# W-F-FC-HX3X.net
KiCad netlist of a schematic drawn in Altium Designer
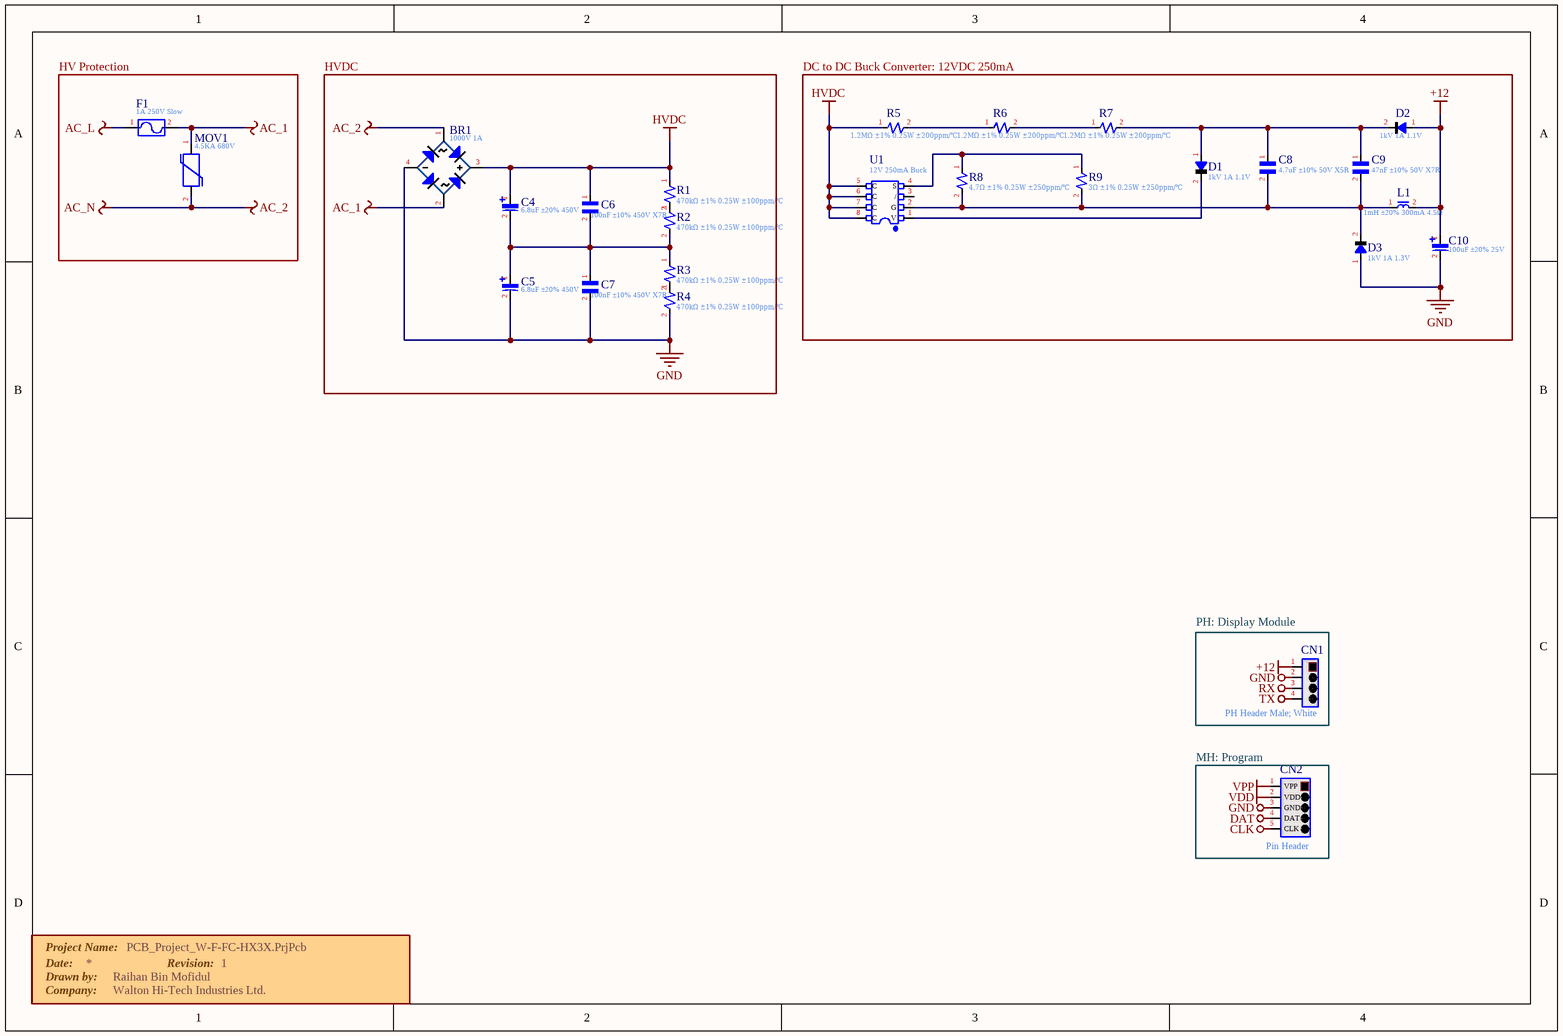
[diagram p0: W-F-FC-HX3X.SchDoc]

(export (version "E")
  (design (tool "Eeschema 10.0.6"))
  (components
    (comp (ref "BR1")
      (value "1000V 1A")
      (footprint "D_SMD_MBS")
      (description "MB10S-10; MBS Bridge Rectifiers RoHS")
      (libsource (lib "RBM_ALTIUM_SCH_LIBRARY") (part "Diode{gt}{gt} Bridge Rectifier"))
    )
    (comp (ref "C4")
      (value "6.8uF ±20% 450V")
      (footprint "C_SMD_Ø10*13mm")
      (description "VKME1302W6R8MV; 10x13mm Aluminum Electrolytic Capacitors - SMD RoHS")
      (libsource (lib "RBM_ALTIUM_SCH_LIBRARY") (part "Capacitor{gt}{gt} Polar"))
    )
    (comp (ref "C5")
      (value "6.8uF ±20% 450V")
      (footprint "C_SMD_Ø10*13mm")
      (description "VKME1302W6R8MV; 10x13mm Aluminum Electrolytic Capacitors - SMD RoHS")
      (libsource (lib "RBM_ALTIUM_SCH_LIBRARY") (part "Capacitor{gt}{gt} Polar"))
    )
    (comp (ref "C6")
      (value "100nF ±10% 450V X7R")
      (footprint "C_1206")
      (description "NM1206B104K451CEGN; 1206 Multilayer Ceramic Capacitors MLCC - SMD/SMT RoHS")
      (libsource (lib "RBM_ALTIUM_SCH_LIBRARY") (part "Capacitor{gt}{gt} Non-Polar"))
    )
    (comp (ref "C7")
      (value "100nF ±10% 450V X7R")
      (footprint "C_1206")
      (description "NM1206B104K451CEGN; 1206 Multilayer Ceramic Capacitors MLCC - SMD/SMT RoHS")
      (libsource (lib "RBM_ALTIUM_SCH_LIBRARY") (part "Capacitor{gt}{gt} Non-Polar"))
    )
    (comp (ref "C8")
      (value "4.7uF ±10% 50V X5R")
      (footprint "C_0805")
      (description "CL21A475KBQNNNE; 0805 Multilayer Ceramic Capacitors MLCC - SMD/SMT RoHS")
      (libsource (lib "RBM_ALTIUM_SCH_LIBRARY") (part "Capacitor{gt}{gt} Non-Polar"))
    )
    (comp (ref "C9")
      (value "47nF ±10% 50V X7R")
      (footprint "C_0805")
      (description "CL21B473KBANNNC; 0805 Multilayer Ceramic Capacitors MLCC - SMD/SMT RoHS")
      (libsource (lib "RBM_ALTIUM_SCH_LIBRARY") (part "Capacitor{gt}{gt} Non-Polar"))
    )
    (comp (ref "C10")
      (value "100uF ±20% 25V")
      (footprint "C_SMD_Ø6.3*5.4mm")
      (description "SMD,6.3x5.4mm Aluminum Electrolytic Capacitors - SMD RoHS")
      (libsource (lib "RBM_ALTIUM_SCH_LIBRARY") (part "Capacitor{gt}{gt} Polar"))
    )
    (comp (ref "CN1")
      (value "PH Header Male; White")
      (footprint "CN_4P_A2001WR-S-XP-LCP")
      (description "A2001WR-S-4P; Pin 0.079\"(2.00mm) 4 SMD,P=2mm Wire To Board / Wire To Wire Connector RoHS")
      (libsource (lib "RBM_ALTIUM_SCH_LIBRARY") (part "Connector{gt}{gt} 4Pins"))
    )
    (comp (ref "CN2")
      (value "Pin Header")
      (footprint "CN_PIC_MCU_Debugger_RightAngle")
      (libsource (lib "RBM_ALTIUM_SCH_LIBRARY") (part "Connector{gt}{gt} PIC Program"))
    )
    (comp (ref "D1")
      (value "1kV 1A 1.1V")
      (footprint "D_DO-214AC")
      (description "MDD  M7; SMA(DO-214AC) Diodes - General Purpose RoHS")
      (libsource (lib "RBM_ALTIUM_SCH_LIBRARY") (part "Diode{gt}{gt} General Purpose"))
    )
    (comp (ref "D2")
      (value "1kV 1A 1.1V")
      (footprint "D_DO-214AC")
      (description "MDD  M7; SMA(DO-214AC) Diodes - General Purpose RoHS")
      (libsource (lib "") (part "Diode{gt}{gt} General Purpose_1"))
    )
    (comp (ref "D3")
      (value "1kV 1A 1.3V")
      (footprint "D_DO-214AC")
      (description "LGE RS1M; 1A 500ns SMA Diodes - Rectifiers - Fast Recovery RoHS")
      (libsource (lib "") (part "Diode{gt}{gt} General Purpose_2"))
    )
    (comp (ref "F1")
      (value "1A 250V Slow")
      (footprint "F_SQUARE_8.5*8_P5.08")
      (libsource (lib "RBM_ALTIUM_SCH_LIBRARY") (part "Fuse"))
    )
    (comp (ref "L1")
      (value "1mH ±20% 300mA 4.5Ω")
      (footprint "L_SMD_6.0x6.0x4.5mm")
      (description "YNR6045-102M; SMD,6.0x6.0x4.5mm Power Inductors RoHS")
      (libsource (lib "RBM_ALTIUM_SCH_LIBRARY") (part "Inductor{gt}{gt} General Purpose"))
    )
    (comp (ref "MOV1")
      (value "4.5KA 680V")
      (footprint "MOV_14D561K")
      (description "VDR-14D681K; 560V 1120V 4.5KA 680V Through Hole,P=7.5MM Varistors RoHS")
      (libsource (lib "RBM_ALTIUM_SCH_LIBRARY") (part "Varistor"))
    )
    (comp (ref "R1")
      (value "470kΩ ±1% 0.25W ±100ppm/℃")
      (footprint "R_1206")
      (description "RK73H2BTTD4703F; 1206 Chip Resistor - Surface Mount RoHS")
      (libsource (lib "RBM_ALTIUM_SCH_LIBRARY") (part "Resistor{gt}{gt} General Purpose"))
    )
    (comp (ref "R2")
      (value "470kΩ ±1% 0.25W ±100ppm/℃")
      (footprint "R_1206")
      (description "RK73H2BTTD4703F; 1206 Chip Resistor - Surface Mount RoHS")
      (libsource (lib "RBM_ALTIUM_SCH_LIBRARY") (part "Resistor{gt}{gt} General Purpose"))
    )
    (comp (ref "R3")
      (value "470kΩ ±1% 0.25W ±100ppm/℃")
      (footprint "R_1206")
      (description "RK73H2BTTD4703F; 1206 Chip Resistor - Surface Mount RoHS")
      (libsource (lib "RBM_ALTIUM_SCH_LIBRARY") (part "Resistor{gt}{gt} General Purpose"))
    )
    (comp (ref "R4")
      (value "470kΩ ±1% 0.25W ±100ppm/℃")
      (footprint "R_1206")
      (description "RK73H2BTTD4703F; 1206 Chip Resistor - Surface Mount RoHS")
      (libsource (lib "RBM_ALTIUM_SCH_LIBRARY") (part "Resistor{gt}{gt} General Purpose"))
    )
    (comp (ref "R5")
      (value "1.2MΩ ±1% 0.25W ±200ppm/℃")
      (footprint "R_1206")
      (description "RK73H2BTTD1204F; 1206 Chip Resistor - Surface Mount RoHS")
      (libsource (lib "RBM_ALTIUM_SCH_LIBRARY") (part "Resistor{gt}{gt} General Purpose"))
    )
    (comp (ref "R6")
      (value "1.2MΩ ±1% 0.25W ±200ppm/℃")
      (footprint "R_1206")
      (description "RK73H2BTTD1204F; 1206 Chip Resistor - Surface Mount RoHS")
      (libsource (lib "RBM_ALTIUM_SCH_LIBRARY") (part "Resistor{gt}{gt} General Purpose"))
    )
    (comp (ref "R7")
      (value "1.2MΩ ±1% 0.25W ±200ppm/℃")
      (footprint "R_1206")
      (description "RK73H2BTTD1204F; 1206 Chip Resistor - Surface Mount RoHS")
      (libsource (lib "RBM_ALTIUM_SCH_LIBRARY") (part "Resistor{gt}{gt} General Purpose"))
    )
    (comp (ref "R8")
      (value "4.7Ω ±1% 0.25W ±250ppm/℃")
      (footprint "R_1206")
      (description "RS-06L4R70FT; 1206 Chip Resistor - Surface Mount RoHS")
      (libsource (lib "RBM_ALTIUM_SCH_LIBRARY") (part "Resistor{gt}{gt} General Purpose"))
    )
    (comp (ref "R9")
      (value "3Ω ±1% 0.25W ±250ppm/℃")
      (footprint "R_1206")
      (description "RS-06L3R00FT; 1206 Chip Resistor - Surface Mount RoHS")
      (libsource (lib "RBM_ALTIUM_SCH_LIBRARY") (part "Resistor{gt}{gt} General Purpose"))
    )
    (comp (ref "U1")
      (value "12V 250mA Buck")
      (footprint "U_SOP-8")
      (description "OB2225MCPA; SOP8 Switching Controllers RoHS")
      (libsource (lib "RBM_ALTIUM_SCH_LIBRARY") (part "IC{gt}{gt} OB-SMPS 8pins"))
    )
  )
  (nets
    (net (code "1") (name "+12") (class "Default")
      (node (ref "C10") (pin "1") (pinfunction "1_1") (pintype "passive"))
      (node (ref "CN1") (pin "1") (pinfunction "1_1") (pintype "passive"))
      (node (ref "D2") (pin "1") (pinfunction "A_1") (pintype "passive"))
      (node (ref "L1") (pin "2") (pinfunction "2_2") (pintype "passive"))
    )
    (net (code "2") (name "AC_1") (class "Default")
      (node (ref "BR1") (pin "2") (pinfunction "AC_2") (pintype "passive"))
      (node (ref "F1") (pin "2") (pinfunction "2_2") (pintype "passive"))
      (node (ref "MOV1") (pin "1") (pinfunction "1_1") (pintype "passive"))
    )
    (net (code "3") (name "AC_2") (class "Default")
      (node (ref "BR1") (pin "1") (pinfunction "AC_1") (pintype "passive"))
      (node (ref "MOV1") (pin "2") (pinfunction "2_2") (pintype "passive"))
    )
    (net (code "4") (name "AC_L") (class "Default")
      (node (ref "F1") (pin "1") (pinfunction "1_1") (pintype "passive"))
    )
    (net (code "5") (name "CLK") (class "Default")
      (node (ref "CN2") (pin "5") (pinfunction "CLK_5") (pintype "passive"))
    )
    (net (code "6") (name "DAT") (class "Default")
      (node (ref "CN2") (pin "4") (pinfunction "DAT_4") (pintype "passive"))
    )
    (net (code "7") (name "GND") (class "Default")
      (node (ref "BR1") (pin "4") (pinfunction "vss_4") (pintype "passive"))
      (node (ref "C10") (pin "2") (pinfunction "2_2") (pintype "passive"))
      (node (ref "C5") (pin "2") (pinfunction "2_2") (pintype "passive"))
      (node (ref "C7") (pin "2") (pinfunction "2_2") (pintype "passive"))
      (node (ref "CN1") (pin "2") (pinfunction "2_2") (pintype "passive"))
      (node (ref "CN2") (pin "3") (pinfunction "GND_3") (pintype "passive"))
      (node (ref "D3") (pin "1") (pinfunction "A_1") (pintype "passive"))
      (node (ref "R4") (pin "2") (pinfunction "2_2") (pintype "passive"))
    )
    (net (code "8") (name "HVDC") (class "Default")
      (node (ref "BR1") (pin "3") (pinfunction "VCC_3") (pintype "passive"))
      (node (ref "C4") (pin "1") (pinfunction "1_1") (pintype "passive"))
      (node (ref "C6") (pin "1") (pinfunction "1_1") (pintype "passive"))
      (node (ref "R1") (pin "1") (pinfunction "1_1") (pintype "passive"))
      (node (ref "R5") (pin "1") (pinfunction "1_1") (pintype "passive"))
      (node (ref "U1") (pin "5") (pinfunction "C_5") (pintype "passive"))
      (node (ref "U1") (pin "6") (pinfunction "C_6") (pintype "passive"))
      (node (ref "U1") (pin "7") (pinfunction "C_7") (pintype "passive"))
      (node (ref "U1") (pin "8") (pinfunction "C_8") (pintype "passive"))
    )
    (net (code "9") (name "Net-(C4-Pad2)") (class "Default")
      (node (ref "C4") (pin "2") (pinfunction "2_2") (pintype "passive"))
      (node (ref "C5") (pin "1") (pinfunction "1_1") (pintype "passive"))
      (node (ref "C6") (pin "2") (pinfunction "2_2") (pintype "passive"))
      (node (ref "C7") (pin "1") (pinfunction "1_1") (pintype "passive"))
      (node (ref "R2") (pin "2") (pinfunction "2_2") (pintype "passive"))
      (node (ref "R3") (pin "1") (pinfunction "1_1") (pintype "passive"))
    )
    (net (code "10") (name "Net-(D1-A)") (class "Default")
      (node (ref "C8") (pin "1") (pinfunction "1_1") (pintype "passive"))
      (node (ref "C9") (pin "1") (pinfunction "1_1") (pintype "passive"))
      (node (ref "D1") (pin "1") (pinfunction "A_1") (pintype "passive"))
      (node (ref "D2") (pin "2") (pinfunction "K_2") (pintype "passive"))
      (node (ref "R7") (pin "2") (pinfunction "2_2") (pintype "passive"))
    )
    (net (code "11") (name "Net-(D1-K)") (class "Default")
      (node (ref "D1") (pin "2") (pinfunction "K_2") (pintype "passive"))
      (node (ref "U1") (pin "1") (pinfunction "V_1") (pintype "passive"))
    )
    (net (code "12") (name "Net-(D3-K)") (class "Default")
      (node (ref "C8") (pin "2") (pinfunction "2_2") (pintype "passive"))
      (node (ref "C9") (pin "2") (pinfunction "2_2") (pintype "passive"))
      (node (ref "D3") (pin "2") (pinfunction "K_2") (pintype "passive"))
      (node (ref "L1") (pin "1") (pinfunction "1_1") (pintype "passive"))
      (node (ref "R8") (pin "2") (pinfunction "2_2") (pintype "passive"))
      (node (ref "R9") (pin "2") (pinfunction "2_2") (pintype "passive"))
      (node (ref "U1") (pin "2") (pinfunction "G_2") (pintype "passive"))
    )
    (net (code "13") (name "Net-(R1-Pad2)") (class "Default")
      (node (ref "R1") (pin "2") (pinfunction "2_2") (pintype "passive"))
      (node (ref "R2") (pin "1") (pinfunction "1_1") (pintype "passive"))
    )
    (net (code "14") (name "Net-(R3-Pad2)") (class "Default")
      (node (ref "R3") (pin "2") (pinfunction "2_2") (pintype "passive"))
      (node (ref "R4") (pin "1") (pinfunction "1_1") (pintype "passive"))
    )
    (net (code "15") (name "Net-(R5-Pad2)") (class "Default")
      (node (ref "R5") (pin "2") (pinfunction "2_2") (pintype "passive"))
      (node (ref "R6") (pin "1") (pinfunction "1_1") (pintype "passive"))
    )
    (net (code "16") (name "Net-(R6-Pad2)") (class "Default")
      (node (ref "R6") (pin "2") (pinfunction "2_2") (pintype "passive"))
      (node (ref "R7") (pin "1") (pinfunction "1_1") (pintype "passive"))
    )
    (net (code "17") (name "Net-(U1-S)") (class "Default")
      (node (ref "R8") (pin "1") (pinfunction "1_1") (pintype "passive"))
      (node (ref "R9") (pin "1") (pinfunction "1_1") (pintype "passive"))
      (node (ref "U1") (pin "4") (pinfunction "S_4") (pintype "passive"))
    )
    (net (code "18") (name "RX") (class "Default")
      (node (ref "CN1") (pin "3") (pinfunction "3_3") (pintype "passive"))
    )
    (net (code "19") (name "TX") (class "Default")
      (node (ref "CN1") (pin "4") (pinfunction "4_4") (pintype "passive"))
    )
    (net (code "20") (name "VDD") (class "Default")
      (node (ref "CN2") (pin "2") (pinfunction "VDD_2") (pintype "passive"))
    )
    (net (code "21") (name "VPP") (class "Default")
      (node (ref "CN2") (pin "1") (pinfunction "VPP_1") (pintype "passive"))
    )
    (net (code "22") (name "unconnected-(U1-{slash}-Pad3)") (class "Default")
      (node (ref "U1") (pin "3") (pinfunction "/_3") (pintype "passive"))
    )
  )
)
